# Light_Cube.net
KiCad netlist of a schematic drawn in EAGLE
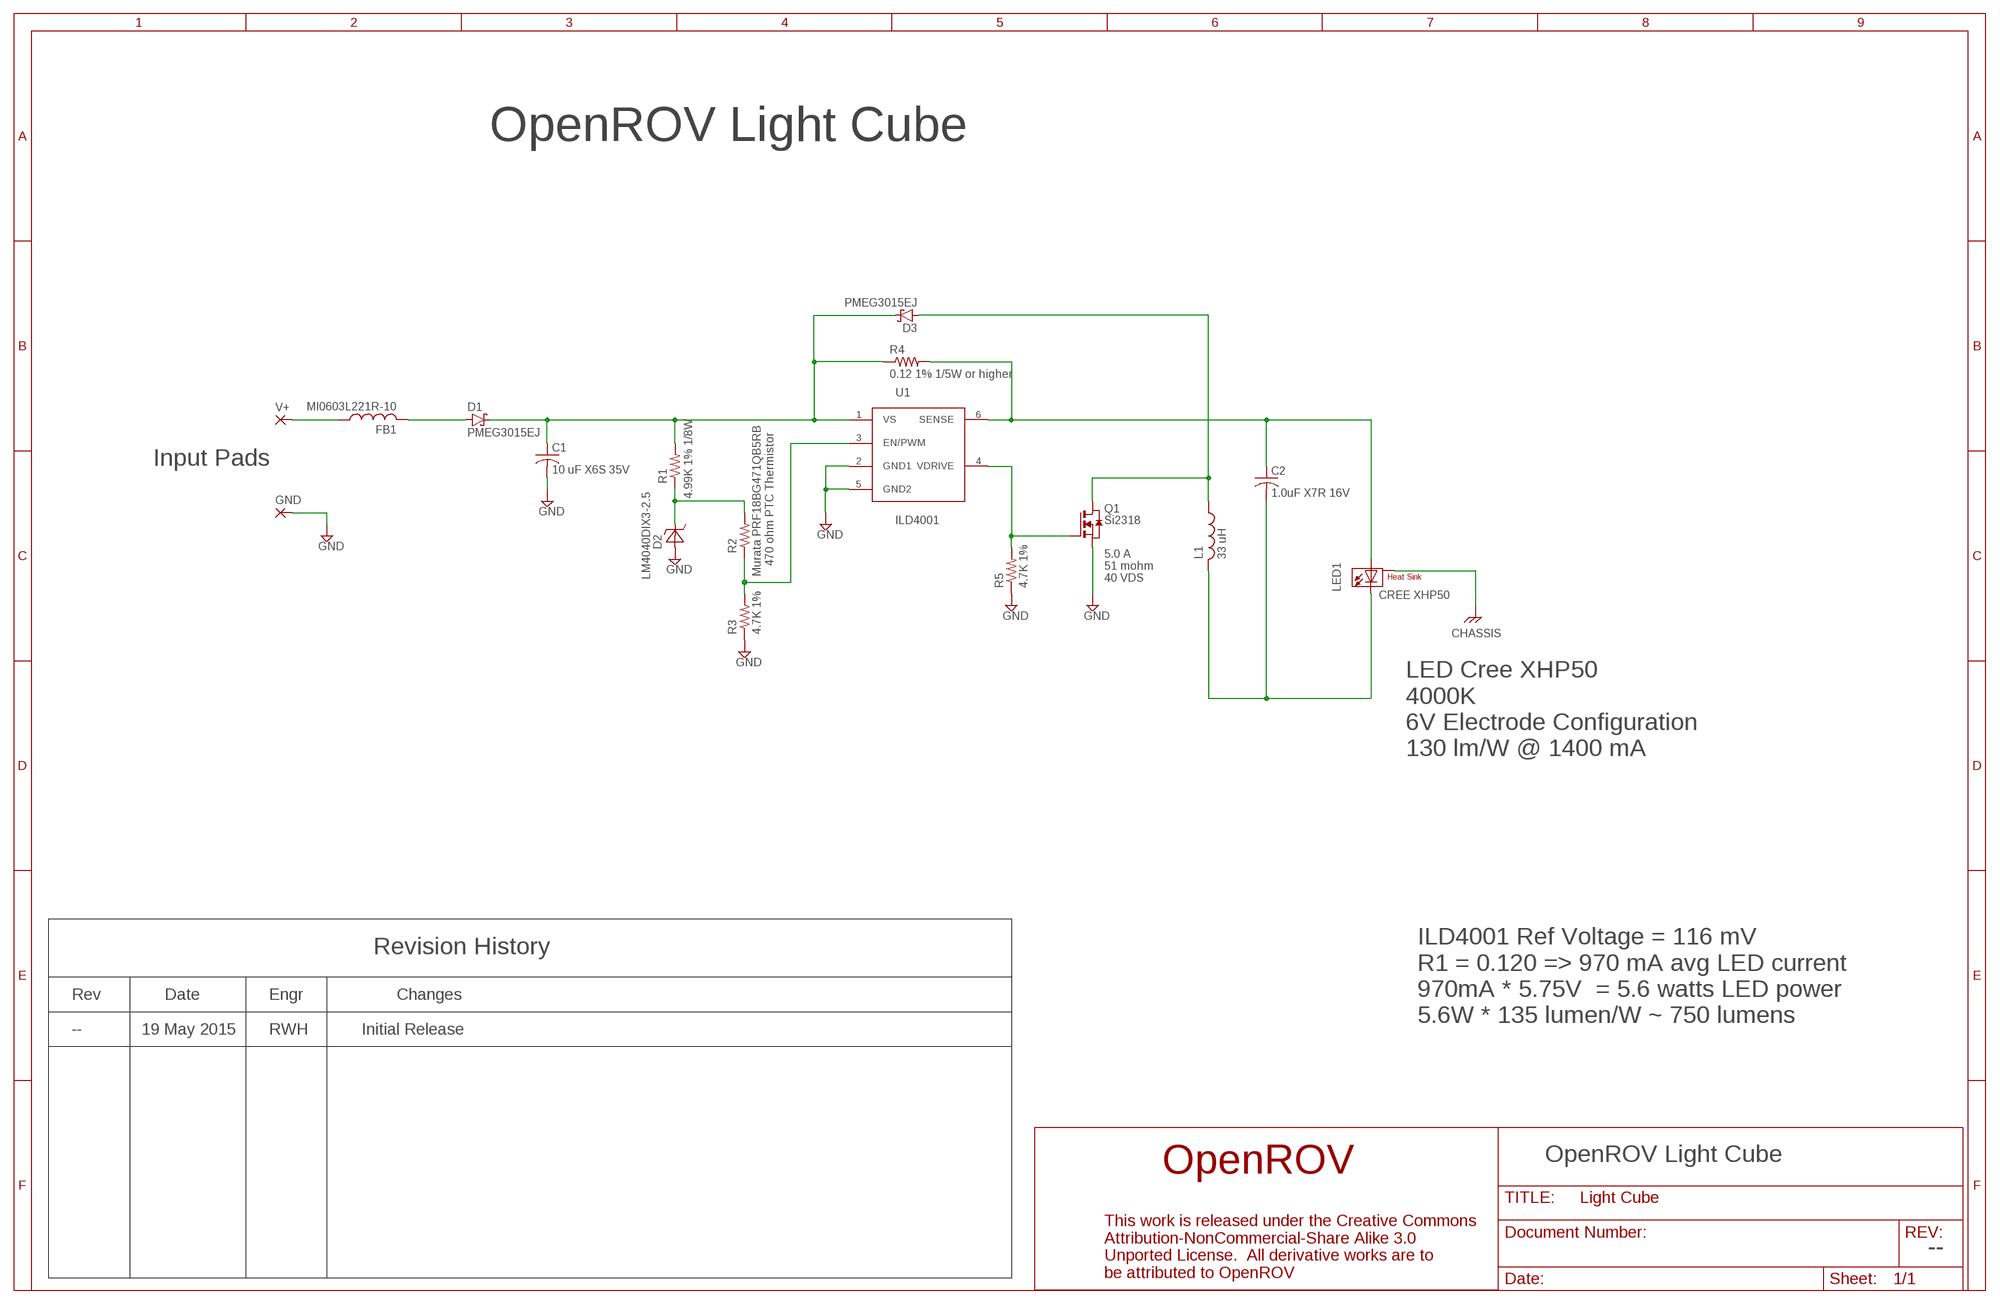
[diagram p0: schematic, sheet 1]

(export (version "E")
  (design (tool "Eeschema 10.0.6"))
  (components
    (comp (ref "C1")
      (value "10 uF X6S 35V")
      (footprint "eagle-import:R0805")
      (libsource (lib "eagle-import") (part "CAP0805"))
    )
    (comp (ref "C2")
      (value "1.0uF X7R 16V")
      (footprint "eagle-import:R0603")
      (libsource (lib "eagle-import") (part "CAP0603"))
    )
    (comp (ref "D1")
      (value "PMEG3015EJ")
      (footprint "eagle-import:SOD323")
      (libsource (lib "eagle-import") (part "SCHOTTKYSOD323"))
    )
    (comp (ref "D2")
      (value "LM4040DIX3-2.5")
      (footprint "eagle-import:SC70-3")
      (libsource (lib "eagle-import") (part "ZENER-TVS-SC70-3"))
    )
    (comp (ref "D3")
      (value "PMEG3015EJ")
      (footprint "eagle-import:SOD323")
      (libsource (lib "eagle-import") (part "SCHOTTKYSOD323"))
    )
    (comp (ref "FB1")
      (value "MI0603L221R-10")
      (footprint "eagle-import:R0603")
      (libsource (lib "eagle-import") (part "FERRITESIZE_0603"))
    )
    (comp (ref "GND")
      (value "SMD_PAD3/3")
      (footprint "eagle-import:SMD_3_3")
      (libsource (lib "eagle-import") (part "SMD_PAD3/3"))
    )
    (comp (ref "L1")
      (value "33 uH")
      (footprint "eagle-import:INDUCTOR_LAIRD_TYS6045")
      (libsource (lib "eagle-import") (part "INDUCTOR-LAIRD_TYS6045"))
    )
    (comp (ref "LED1")
      (value "CREE XHP50")
      (footprint "eagle-import:CREE_XHP50_6V")
      (libsource (lib "eagle-import") (part "LED_WITH_HEATSINK-CREE_XHP50_6V"))
    )
    (comp (ref "Q1")
      (value "Si2318")
      (footprint "eagle-import:SOT23")
      (libsource (lib "eagle-import") (part "NMOS-FETSOT23"))
    )
    (comp (ref "R1")
      (value "4.99K 1% 1/8W")
      (footprint "eagle-import:R0402")
      (libsource (lib "eagle-import") (part "RESISTOR-0402"))
    )
    (comp (ref "R2")
      (value "Murata PRF18BG471QB5RB")
      (footprint "eagle-import:R0603")
      (libsource (lib "eagle-import") (part "RESISTOR-0603"))
    )
    (comp (ref "R3")
      (value "4.7K 1%")
      (footprint "eagle-import:R0402")
      (libsource (lib "eagle-import") (part "RESISTOR-0402"))
    )
    (comp (ref "R4")
      (value "0.12 1% 1/5W or higher")
      (footprint "eagle-import:R0603")
      (libsource (lib "eagle-import") (part "RESISTOR-0603"))
    )
    (comp (ref "R5")
      (value "4.7K 1%")
      (footprint "eagle-import:R0402")
      (libsource (lib "eagle-import") (part "RESISTOR-0402"))
    )
    (comp (ref "U1")
      (value "ILD4001")
      (footprint "eagle-import:SC74_INFINEON")
      (libsource (lib "eagle-import") (part "ILD4001"))
    )
    (comp (ref "V+")
      (value "SMD_PAD-2/2")
      (footprint "eagle-import:SMD_2_2")
      (libsource (lib "eagle-import") (part "SMD_PAD-2/2"))
    )
  )
  (nets
    (net (code "1") (name "CHASSIS") (class "Default")
      (node (ref "LED1") (pin "SINK") (pinfunction "HEATSINK_SINK") (pintype "passive"))
    )
    (net (code "2") (name "GND") (class "Default")
      (node (ref "C1") (pin "2") (pinfunction "2_2") (pintype "passive"))
      (node (ref "D2") (pin "2") (pinfunction "A_2") (pintype "passive"))
      (node (ref "GND") (pin "1") (pinfunction "P_1") (pintype "passive"))
      (node (ref "Q1") (pin "2") (pinfunction "S_2") (pintype "passive"))
      (node (ref "R3") (pin "1") (pinfunction "1_1") (pintype "passive"))
      (node (ref "R5") (pin "1") (pinfunction "1_1") (pintype "passive"))
      (node (ref "U1") (pin "2") (pinfunction "GND1_2") (pintype "bidirectional"))
      (node (ref "U1") (pin "5") (pinfunction "GND2_5") (pintype "bidirectional"))
    )
    (net (code "3") (name "Net-(D1-PadA)") (class "Default")
      (node (ref "D1") (pin "A") (pinfunction "A_A") (pintype "passive"))
      (node (ref "FB1") (pin "2") (pinfunction "2_2") (pintype "passive"))
    )
    (net (code "4") (name "Net-(D2-C)") (class "Default")
      (node (ref "D2") (pin "1") (pinfunction "C_1") (pintype "passive"))
      (node (ref "R1") (pin "1") (pinfunction "1_1") (pintype "passive"))
      (node (ref "R2") (pin "2") (pinfunction "2_2") (pintype "passive"))
    )
    (net (code "5") (name "Net-(L1-1)") (class "Default")
      (node (ref "D3") (pin "A") (pinfunction "A_A") (pintype "passive"))
      (node (ref "L1") (pin "P$1") (pinfunction "1_P$1") (pintype "passive"))
      (node (ref "Q1") (pin "3") (pinfunction "D_3") (pintype "passive"))
    )
    (net (code "6") (name "Net-(L1-2)") (class "Default")
      (node (ref "C2") (pin "2") (pinfunction "2_2") (pintype "passive"))
      (node (ref "L1") (pin "P$2") (pinfunction "2_P$2") (pintype "passive"))
      (node (ref "LED1") (pin "C") (pinfunction "C_C") (pintype "passive"))
    )
    (net (code "7") (name "Net-(Q1-G)") (class "Default")
      (node (ref "Q1") (pin "1") (pinfunction "G_1") (pintype "passive"))
      (node (ref "R5") (pin "2") (pinfunction "2_2") (pintype "passive"))
      (node (ref "U1") (pin "4") (pinfunction "VDRIVE_4") (pintype "bidirectional"))
    )
    (net (code "8") (name "Net-(U1-EN{slash}PWM)") (class "Default")
      (node (ref "R2") (pin "1") (pinfunction "1_1") (pintype "passive"))
      (node (ref "R3") (pin "2") (pinfunction "2_2") (pintype "passive"))
      (node (ref "U1") (pin "3") (pinfunction "EN/PWM_3") (pintype "bidirectional"))
    )
    (net (code "9") (name "Net-(U1-SENSE)") (class "Default")
      (node (ref "C2") (pin "1") (pinfunction "1_1") (pintype "passive"))
      (node (ref "LED1") (pin "A") (pinfunction "A_A") (pintype "passive"))
      (node (ref "R4") (pin "2") (pinfunction "2_2") (pintype "passive"))
      (node (ref "U1") (pin "6") (pinfunction "SENSE_6") (pintype "bidirectional"))
    )
    (net (code "10") (name "Net-(U1-VS)") (class "Default")
      (node (ref "C1") (pin "1") (pinfunction "1_1") (pintype "passive"))
      (node (ref "D1") (pin "C") (pinfunction "C_C") (pintype "passive"))
      (node (ref "D3") (pin "C") (pinfunction "C_C") (pintype "passive"))
      (node (ref "R1") (pin "2") (pinfunction "2_2") (pintype "passive"))
      (node (ref "R4") (pin "1") (pinfunction "1_1") (pintype "passive"))
      (node (ref "U1") (pin "1") (pinfunction "VS_1") (pintype "bidirectional"))
    )
    (net (code "11") (name "Net-(V+-P)") (class "Default")
      (node (ref "FB1") (pin "1") (pinfunction "1_1") (pintype "passive"))
      (node (ref "V+") (pin "1") (pinfunction "P_1") (pintype "passive"))
    )
  )
)
